# adapter-lt3032.net
KiCad netlist of a schematic drawn in EAGLE
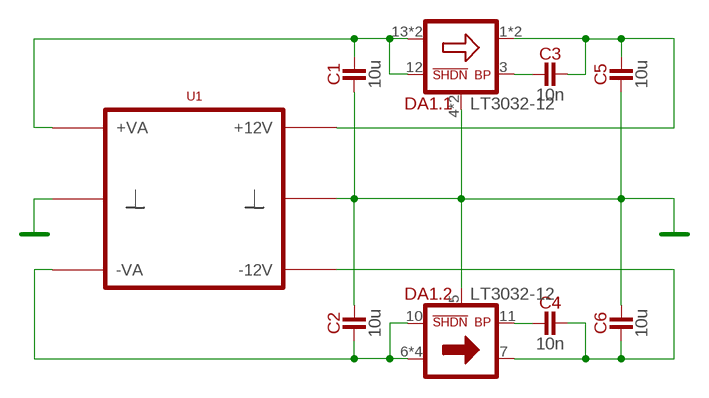
[diagram p0: schematic, sheet 1]

(export (version "E")
  (design (tool "Eeschema 10.0.6"))
  (components
    (comp (ref "C1")
      (value "10u")
      (footprint "eagle-import:C-1206")
      (libsource (lib "eagle-import") (part "C-1206"))
    )
    (comp (ref "C2")
      (value "10u")
      (footprint "eagle-import:C-1206")
      (libsource (lib "eagle-import") (part "C-1206"))
    )
    (comp (ref "C3")
      (value "10n")
      (footprint "eagle-import:C-0805")
      (libsource (lib "eagle-import") (part "C-0805"))
    )
    (comp (ref "C4")
      (value "10n")
      (footprint "eagle-import:C-0805")
      (libsource (lib "eagle-import") (part "C-0805"))
    )
    (comp (ref "C5")
      (value "10u")
      (footprint "eagle-import:C-1206")
      (libsource (lib "eagle-import") (part "C-1206"))
    )
    (comp (ref "C6")
      (value "10u")
      (footprint "eagle-import:C-1206")
      (libsource (lib "eagle-import") (part "C-1206"))
    )
    (comp (ref "DA1")
      (value "LT3032-12")
      (footprint "eagle-import:DE14MA")
      (libsource (lib "eagle-import") (part "LT3032-12"))
    )
    (comp (ref "U1")
      (value "F-DUAL-SUPPLY-BOARD")
      (footprint "eagle-import:F-DIP8-HEATSINK-NOSILK")
      (libsource (lib "eagle-import") (part "F-DUAL-SUPPLY-BOARD"))
    )
  )
  (nets
    (net (code "1") (name "GND") (class "Default")
      (node (ref "C1") (pin "1") (pinfunction "1_1") (pintype "passive"))
      (node (ref "C2") (pin "2") (pinfunction "2_2") (pintype "passive"))
      (node (ref "C5") (pin "1") (pinfunction "1_1") (pintype "passive"))
      (node (ref "C6") (pin "2") (pinfunction "2_2") (pintype "passive"))
      (node (ref "DA1") (pin "15") (pinfunction "GND_15") (pintype "passive"))
      (node (ref "DA1") (pin "4") (pinfunction "GND_4") (pintype "passive"))
      (node (ref "DA1") (pin "5") (pinfunction "GND_5") (pintype "passive"))
      (node (ref "U1") (pin "2") (pinfunction "GND1_2") (pintype "bidirectional"))
      (node (ref "U1") (pin "3") (pinfunction "GND1_3") (pintype "bidirectional"))
      (node (ref "U1") (pin "6") (pinfunction "GND_6") (pintype "bidirectional"))
      (node (ref "U1") (pin "7") (pinfunction "GND_7") (pintype "bidirectional"))
      (node (ref "U1") (pin "P$1") (pinfunction "GND_P$1") (pintype "bidirectional"))
    )
    (net (code "2") (name "Net-(DA1A-BYP)") (class "Default")
      (node (ref "C3") (pin "1") (pinfunction "1_1") (pintype "passive"))
      (node (ref "DA1") (pin "3") (pinfunction "BYP_3") (pintype "passive"))
    )
    (net (code "3") (name "Net-(DA1A-~{SHDN})") (class "Default")
      (node (ref "C1") (pin "2") (pinfunction "2_2") (pintype "passive"))
      (node (ref "DA1") (pin "12") (pinfunction "~{SHDN}_12") (pintype "passive"))
      (node (ref "DA1") (pin "13") (pinfunction "IN_13") (pintype "passive"))
      (node (ref "DA1") (pin "14") (pinfunction "IN_14") (pintype "passive"))
      (node (ref "U1") (pin "1") (pinfunction "P+VA_1") (pintype "bidirectional"))
    )
    (net (code "4") (name "Net-(DA1B-BYP)") (class "Default")
      (node (ref "C4") (pin "1") (pinfunction "1_1") (pintype "passive"))
      (node (ref "DA1") (pin "11") (pinfunction "BYP_11") (pintype "passive"))
    )
    (net (code "5") (name "Net-(DA1B-OUT)") (class "Default")
      (node (ref "C4") (pin "2") (pinfunction "2_2") (pintype "passive"))
      (node (ref "C6") (pin "1") (pinfunction "1_1") (pintype "passive"))
      (node (ref "DA1") (pin "7") (pinfunction "OUT_7") (pintype "passive"))
      (node (ref "U1") (pin "5") (pinfunction "P-12V_5") (pintype "bidirectional"))
    )
    (net (code "6") (name "Net-(DA1B-~{SHDN})") (class "Default")
      (node (ref "C2") (pin "1") (pinfunction "1_1") (pintype "passive"))
      (node (ref "DA1") (pin "10") (pinfunction "~{SHDN}_10") (pintype "passive"))
      (node (ref "DA1") (pin "16") (pinfunction "IN_16") (pintype "passive"))
      (node (ref "DA1") (pin "6") (pinfunction "IN_6") (pintype "passive"))
      (node (ref "DA1") (pin "8") (pinfunction "IN_8") (pintype "passive"))
      (node (ref "DA1") (pin "9") (pinfunction "IN_9") (pintype "passive"))
      (node (ref "U1") (pin "4") (pinfunction "P-VA_4") (pintype "bidirectional"))
    )
    (net (code "7") (name "Net-(U1-P+12V)") (class "Default")
      (node (ref "C3") (pin "2") (pinfunction "2_2") (pintype "passive"))
      (node (ref "C5") (pin "2") (pinfunction "2_2") (pintype "passive"))
      (node (ref "DA1") (pin "1") (pinfunction "OUT_1") (pintype "passive"))
      (node (ref "DA1") (pin "2") (pinfunction "OUT_2") (pintype "passive"))
      (node (ref "U1") (pin "8") (pinfunction "P+12V_8") (pintype "bidirectional"))
    )
  )
)
